# fanproject.net
KiCad netlist of a schematic drawn in EAGLE
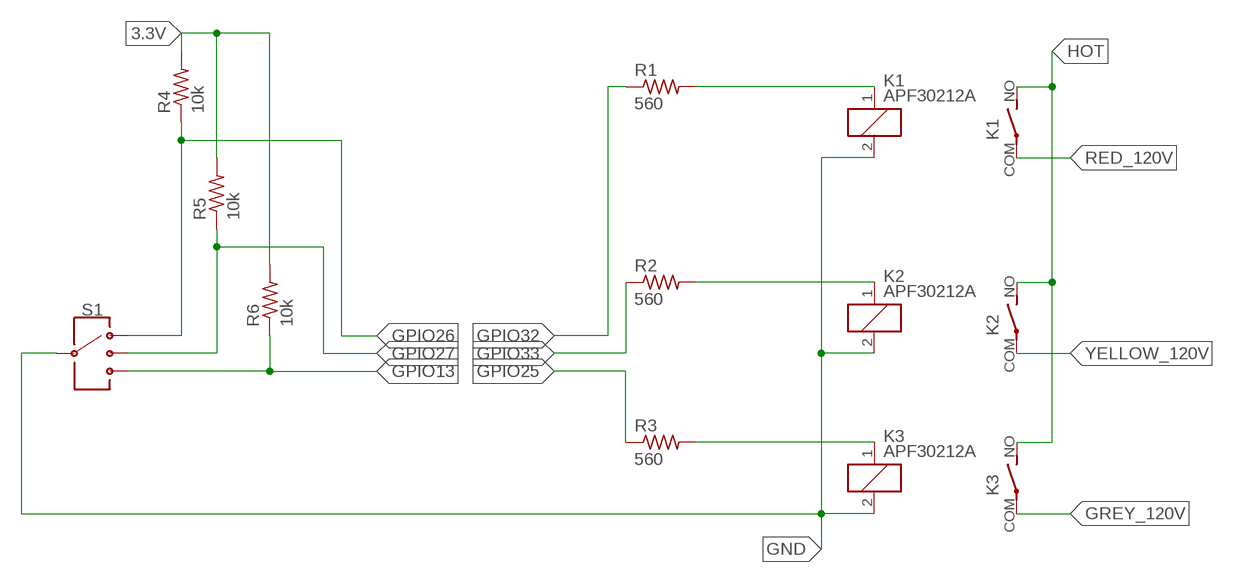
[diagram p0: schematic, sheet 1]

(export (version "E")
  (design (tool "Eeschema 10.0.6"))
  (components
    (comp (ref "K1")
      (value "APF30212A")
      (footprint "eagle-import:APF30212A")
      (libsource (lib "eagle-import") (part "APF30212A"))
    )
    (comp (ref "K2")
      (value "APF30212A")
      (footprint "eagle-import:APF30212A")
      (libsource (lib "eagle-import") (part "APF30212A"))
    )
    (comp (ref "K3")
      (value "APF30212A")
      (footprint "eagle-import:APF30212A")
      (libsource (lib "eagle-import") (part "APF30212A"))
    )
    (comp (ref "R1")
      (value "560")
      (footprint "eagle-import:0204V")
      (libsource (lib "eagle-import") (part "R-US_0204/2V"))
    )
    (comp (ref "R2")
      (value "560")
      (footprint "eagle-import:0204V")
      (libsource (lib "eagle-import") (part "R-US_0204/2V"))
    )
    (comp (ref "R3")
      (value "560")
      (footprint "eagle-import:0204V")
      (libsource (lib "eagle-import") (part "R-US_0204/2V"))
    )
    (comp (ref "R4")
      (value "10k")
      (footprint "eagle-import:0204V")
      (libsource (lib "eagle-import") (part "R-US_0204/2V"))
    )
    (comp (ref "R5")
      (value "10k")
      (footprint "eagle-import:0204V")
      (libsource (lib "eagle-import") (part "R-US_0204/2V"))
    )
    (comp (ref "R6")
      (value "10k")
      (footprint "eagle-import:0204V")
      (libsource (lib "eagle-import") (part "R-US_0204/2V"))
    )
    (comp (ref "S1")
      (value "SWITCH-SP3T-SMD")
      (footprint "eagle-import:SWITCH_SP3T_SMD")
      (libsource (lib "eagle-import") (part "SWITCH-SP3T-SMD"))
    )
  )
  (nets
    (net (code "1") (name "3.3V") (class "Default")
      (node (ref "R4") (pin "2") (pinfunction "2_2") (pintype "passive"))
      (node (ref "R5") (pin "2") (pinfunction "2_2") (pintype "passive"))
      (node (ref "R6") (pin "2") (pinfunction "2_2") (pintype "passive"))
    )
    (net (code "2") (name "GND") (class "Default")
      (node (ref "K1") (pin "2") (pinfunction "2_2") (pintype "passive"))
      (node (ref "K2") (pin "2") (pinfunction "2_2") (pintype "passive"))
      (node (ref "K3") (pin "2") (pinfunction "2_2") (pintype "passive"))
      (node (ref "S1") (pin "3") (pinfunction "3_3") (pintype "bidirectional"))
    )
    (net (code "3") (name "GPIO13") (class "Default")
      (node (ref "R6") (pin "1") (pinfunction "1_1") (pintype "passive"))
      (node (ref "S1") (pin "4") (pinfunction "4_4") (pintype "bidirectional"))
    )
    (net (code "4") (name "GPIO25") (class "Default")
      (node (ref "R3") (pin "1") (pinfunction "1_1") (pintype "passive"))
    )
    (net (code "5") (name "GPIO26") (class "Default")
      (node (ref "R4") (pin "1") (pinfunction "1_1") (pintype "passive"))
      (node (ref "S1") (pin "1") (pinfunction "1_1") (pintype "bidirectional"))
    )
    (net (code "6") (name "GPIO27") (class "Default")
      (node (ref "R5") (pin "1") (pinfunction "1_1") (pintype "passive"))
      (node (ref "S1") (pin "2") (pinfunction "2_2") (pintype "bidirectional"))
    )
    (net (code "7") (name "GPIO32") (class "Default")
      (node (ref "R1") (pin "1") (pinfunction "1_1") (pintype "passive"))
    )
    (net (code "8") (name "GPIO33") (class "Default")
      (node (ref "R2") (pin "1") (pinfunction "1_1") (pintype "passive"))
    )
    (net (code "9") (name "GREY_120V") (class "Default")
      (node (ref "K3") (pin "COM") (pinfunction "P_COM") (pintype "passive"))
    )
    (net (code "10") (name "HOT") (class "Default")
      (node (ref "K1") (pin "NO") (pinfunction "S_NO") (pintype "passive"))
      (node (ref "K2") (pin "NO") (pinfunction "S_NO") (pintype "passive"))
      (node (ref "K3") (pin "NO") (pinfunction "S_NO") (pintype "passive"))
    )
    (net (code "11") (name "Net-(K1-Pad1)") (class "Default")
      (node (ref "K1") (pin "1") (pinfunction "1_1") (pintype "passive"))
      (node (ref "R1") (pin "2") (pinfunction "2_2") (pintype "passive"))
    )
    (net (code "12") (name "Net-(K2-Pad1)") (class "Default")
      (node (ref "K2") (pin "1") (pinfunction "1_1") (pintype "passive"))
      (node (ref "R2") (pin "2") (pinfunction "2_2") (pintype "passive"))
    )
    (net (code "13") (name "Net-(K3-Pad1)") (class "Default")
      (node (ref "K3") (pin "1") (pinfunction "1_1") (pintype "passive"))
      (node (ref "R3") (pin "2") (pinfunction "2_2") (pintype "passive"))
    )
    (net (code "14") (name "RED_120V") (class "Default")
      (node (ref "K1") (pin "COM") (pinfunction "P_COM") (pintype "passive"))
    )
    (net (code "15") (name "YELLOW_120V") (class "Default")
      (node (ref "K2") (pin "COM") (pinfunction "P_COM") (pintype "passive"))
    )
  )
)
